# MCP3424_Temperature_board_V2.net
KiCad netlist of a schematic drawn in EAGLE
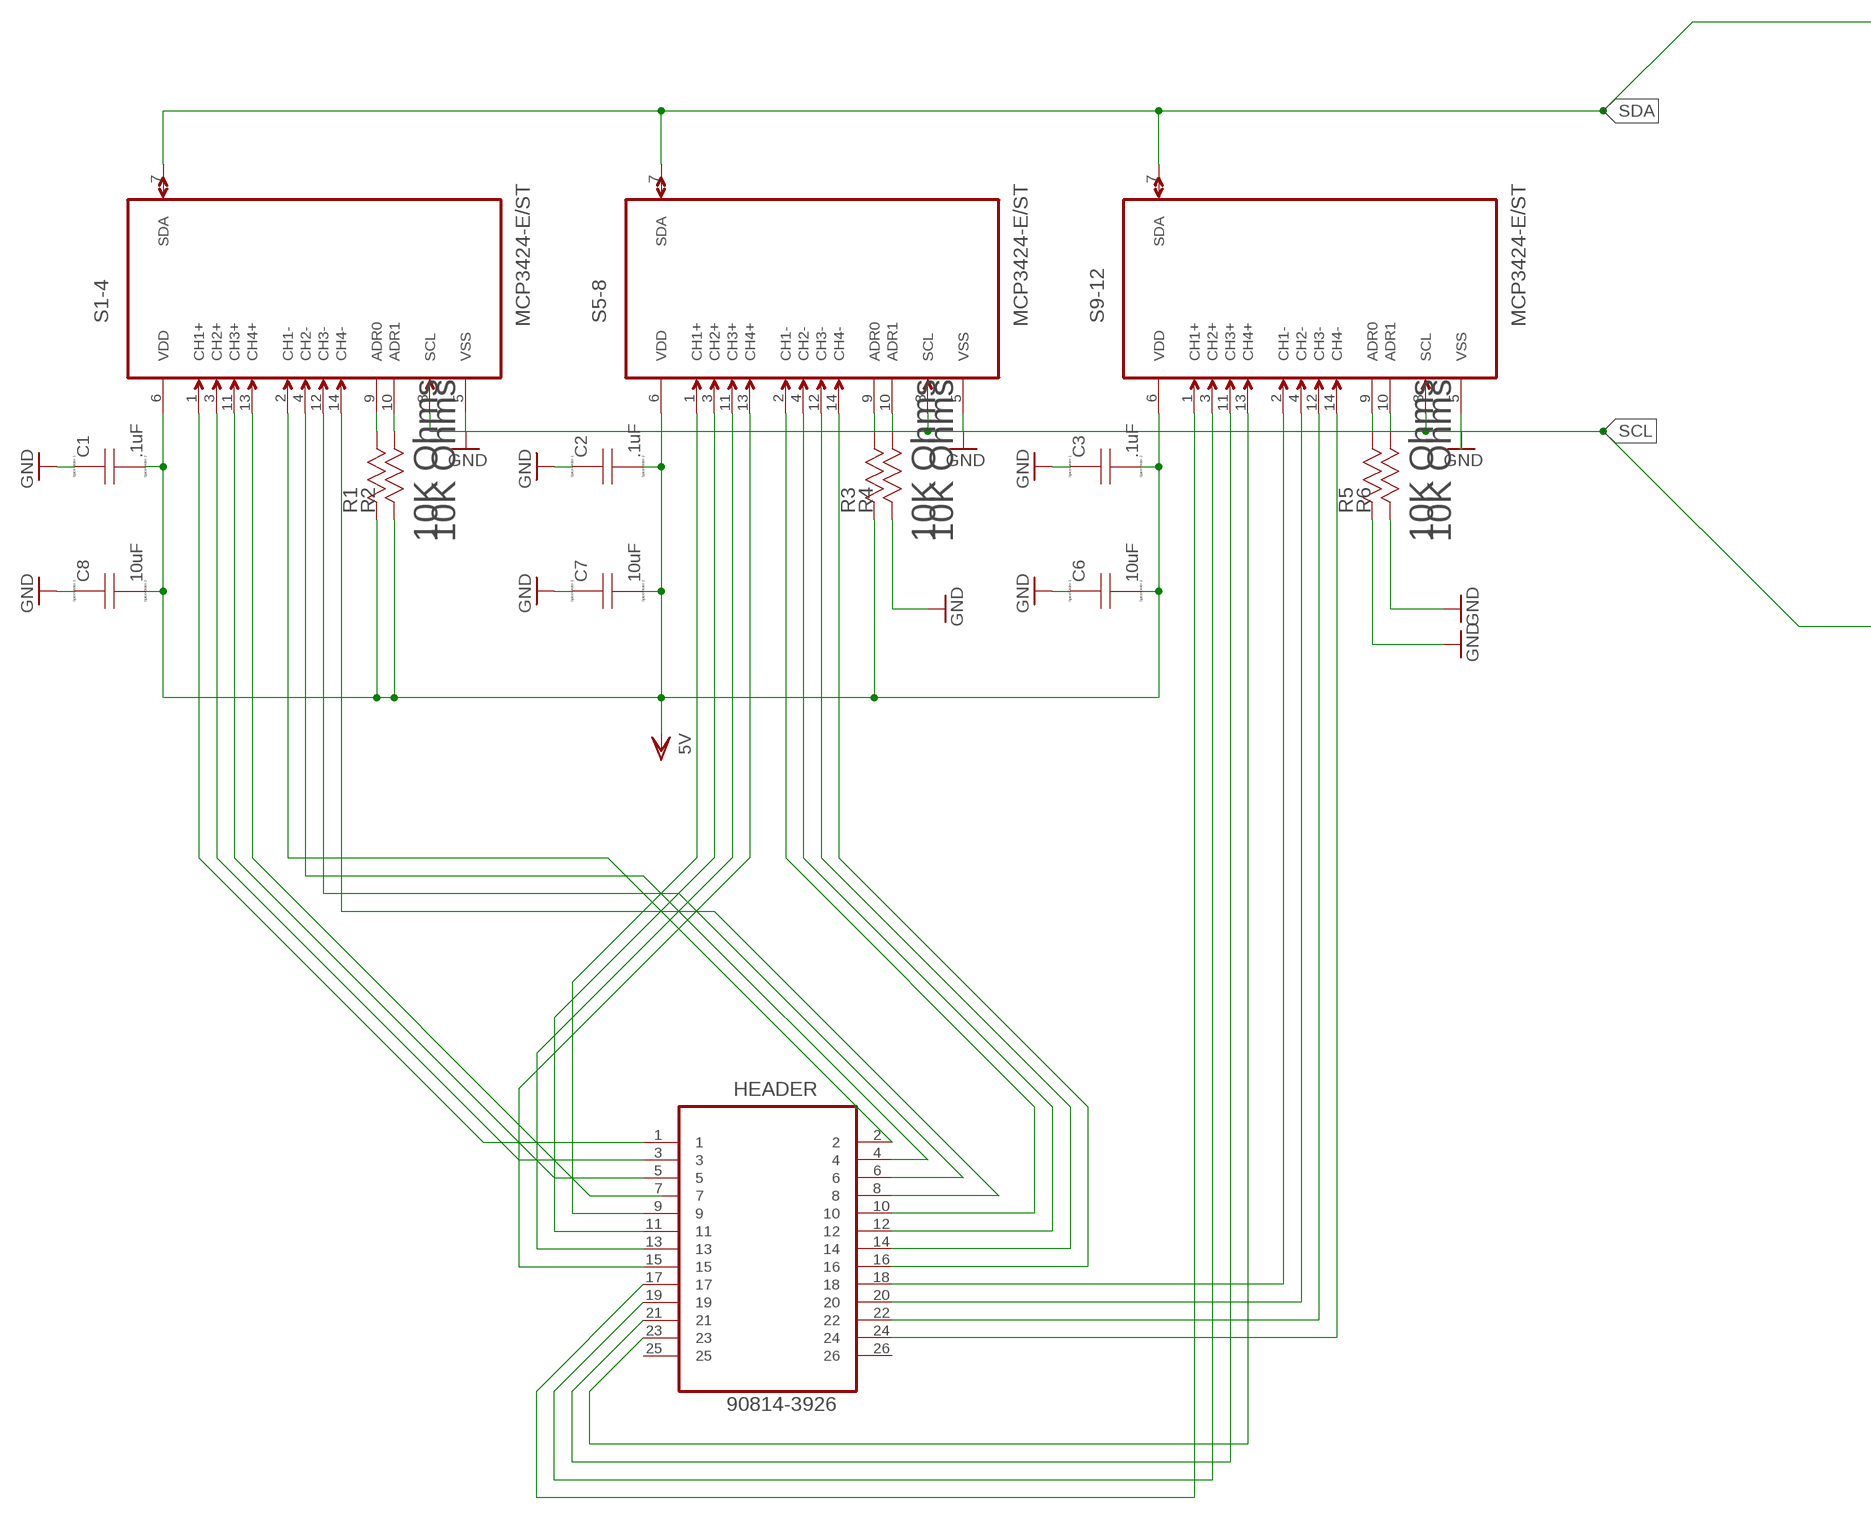
[diagram p0: schematic, sheet 1, part 1 of 2]
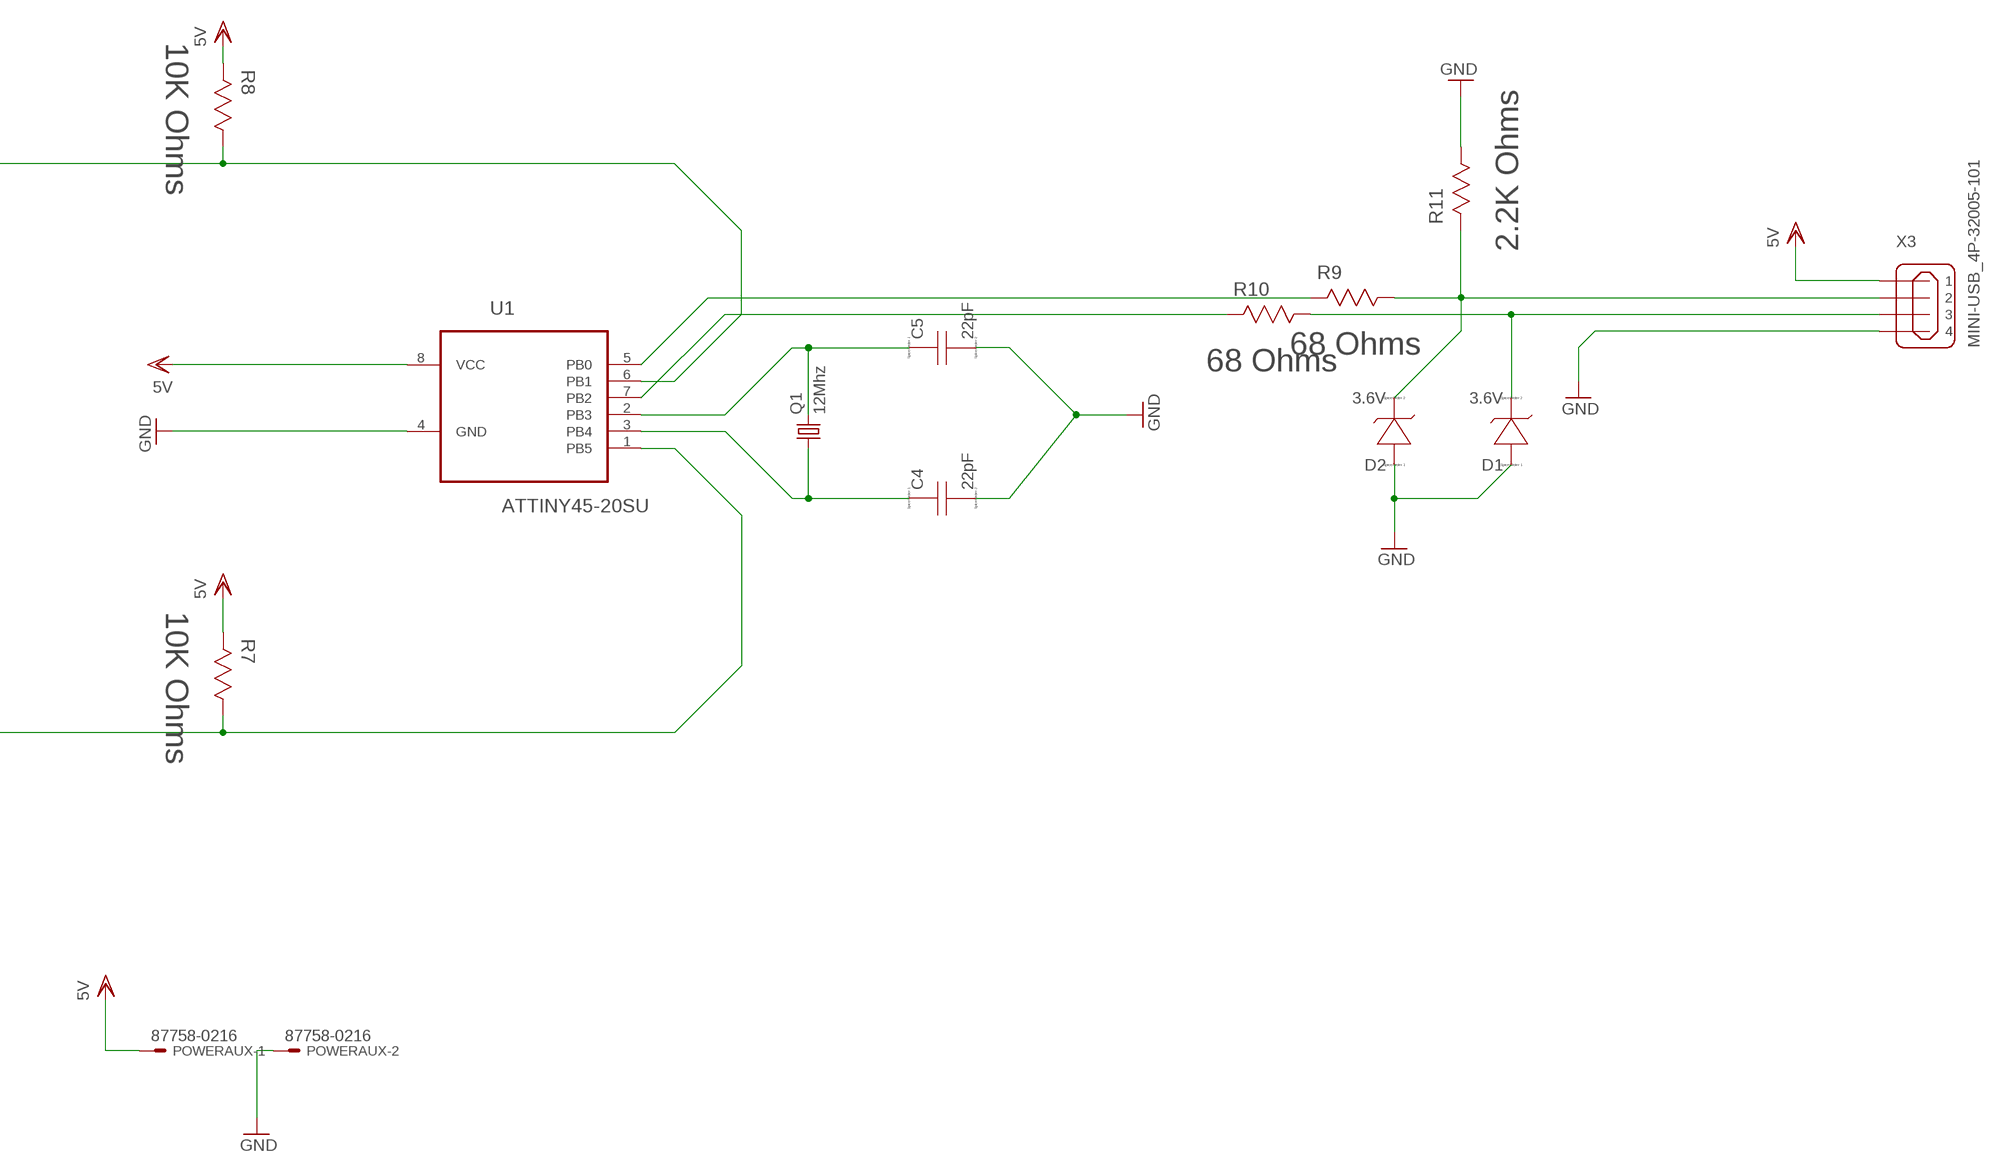
[diagram p1: schematic, sheet 1, part 2 of 2]

(export (version "E")
  (design (tool "Eeschema 10.0.6"))
  (components
    (comp (ref "C1")
      (value ".1uF")
      (footprint "eagle-import:C0805")
      (fields (field (name "MPN") "C0805C104Z3VACTU"))
      (libsource (lib "eagle-import") (part "CAP"))
    )
    (comp (ref "C2")
      (value ".1uF")
      (footprint "eagle-import:C0805")
      (fields (field (name "MPN") "C0805C104Z3VACTU"))
      (libsource (lib "eagle-import") (part "CAP"))
    )
    (comp (ref "C3")
      (value ".1uF")
      (footprint "eagle-import:C0805")
      (fields (field (name "MPN") "C0805C104Z3VACTU"))
      (libsource (lib "eagle-import") (part "CAP"))
    )
    (comp (ref "C4")
      (value "22pF")
      (footprint "eagle-import:C0805")
      (fields (field (name "MPN") "CC0805JRNPO9BN220"))
      (libsource (lib "eagle-import") (part "CAP"))
    )
    (comp (ref "C5")
      (value "22pF")
      (footprint "eagle-import:C0805")
      (fields (field (name "MPN") "CC0805JRNPO9BN220"))
      (libsource (lib "eagle-import") (part "CAP"))
    )
    (comp (ref "C6")
      (value "10uF")
      (footprint "eagle-import:C0805")
      (fields (field (name "MPN") "NOJP106M006RWJ"))
      (libsource (lib "eagle-import") (part "CAP"))
    )
    (comp (ref "C7")
      (value "10uF")
      (footprint "eagle-import:C0805")
      (fields (field (name "MPN") "NOJP106M006RWJ"))
      (libsource (lib "eagle-import") (part "CAP"))
    )
    (comp (ref "C8")
      (value "10uF")
      (footprint "eagle-import:C0805")
      (fields (field (name "MPN") "NOJP106M006RWJ"))
      (libsource (lib "eagle-import") (part "CAP"))
    )
    (comp (ref "D1")
      (value "3.6V")
      (footprint "eagle-import:SOD123")
      (fields (field (name "MPN") "MM3Z3V6T1G"))
      (libsource (lib "eagle-import") (part "ZENER"))
    )
    (comp (ref "D2")
      (value "3.6V")
      (footprint "eagle-import:SOD123")
      (fields (field (name "MPN") "MM3Z3V6T1G"))
      (libsource (lib "eagle-import") (part "ZENER"))
    )
    (comp (ref "HEADER")
      (value "90814-3926")
      (footprint "eagle-import:MOLEX_90814-3926")
      (fields
        (field (name "MF") "MOLEX")
        (field (name "MPN") "50-57-9002")
        (field (name "OC_NEWARK") "77C5436")
      )
      (libsource (lib "eagle-import") (part "90814-3926"))
    )
    (comp (ref "POWERAUX")
      (value "87758-0216")
      (footprint "eagle-import:87758-0216")
      (libsource (lib "eagle-import") (part "87758-0216"))
    )
    (comp (ref "Q1")
      (value "12Mhz")
      (footprint "eagle-import:HC49UP")
      (fields
        (field (name "MF") "Abracon Corporation")
        (field (name "MPN") "ABLS-12.000MHZ-B2-T")
        (field (name "OC_NEWARK") "13J1654")
      )
      (libsource (lib "eagle-import") (part "CRYSTALHC49UP"))
    )
    (comp (ref "R1")
      (value "10K Ohms")
      (footprint "eagle-import:RESC2013X65N")
      (fields
        (field (name "MPN") "P0805Z1002WNT0079")
        (field (name "TOLERANCE") "± 0.05 %")
        (field (name "MF") "VISHAY/DALE")
        (field (name "MPN_1") "CRCW080510K0JNEA")
        (field (name "OC_NEWARK") "52K9797")
      )
      (libsource (lib "eagle-import") (part "P0805Z1002WNT0079"))
    )
    (comp (ref "R2")
      (value "10K Ohms")
      (footprint "eagle-import:RESC2013X65N")
      (fields
        (field (name "MPN") "P0805Z1002WNT0079")
        (field (name "TOLERANCE") "± 0.05 %")
        (field (name "MF") "VISHAY/DALE")
        (field (name "MPN_1") "CRCW080510K0JNEA")
        (field (name "OC_NEWARK") "52K9797")
      )
      (libsource (lib "eagle-import") (part "P0805Z1002WNT0079"))
    )
    (comp (ref "R3")
      (value "10K Ohms")
      (footprint "eagle-import:RESC2013X65N")
      (fields
        (field (name "MPN") "P0805Z1002WNT0079")
        (field (name "TOLERANCE") "± 0.05 %")
        (field (name "MF") "VISHAY/DALE")
        (field (name "MPN_1") "CRCW080510K0JNEA")
        (field (name "OC_NEWARK") "52K9797")
      )
      (libsource (lib "eagle-import") (part "P0805Z1002WNT0079"))
    )
    (comp (ref "R4")
      (value "10K Ohms")
      (footprint "eagle-import:RESC2013X65N")
      (fields
        (field (name "MPN") "P0805Z1002WNT0079")
        (field (name "TOLERANCE") "± 0.05 %")
        (field (name "MF") "VISHAY/DALE")
        (field (name "MPN_1") "CRCW080510K0JNEA")
        (field (name "OC_NEWARK") "52K9797")
      )
      (libsource (lib "eagle-import") (part "P0805Z1002WNT0079"))
    )
    (comp (ref "R5")
      (value "10K Ohms")
      (footprint "eagle-import:RESC2013X65N")
      (fields
        (field (name "MPN") "P0805Z1002WNT0079")
        (field (name "TOLERANCE") "± 0.05 %")
        (field (name "MF") "VISHAY/DALE")
        (field (name "MPN_1") "CRCW080510K0JNEA")
        (field (name "OC_NEWARK") "52K9797")
      )
      (libsource (lib "eagle-import") (part "P0805Z1002WNT0079"))
    )
    (comp (ref "R6")
      (value "10K Ohms")
      (footprint "eagle-import:RESC2013X65N")
      (fields
        (field (name "MPN") "P0805Z1002WNT0079")
        (field (name "TOLERANCE") "± 0.05 %")
        (field (name "MF") "VISHAY/DALE")
        (field (name "MPN_1") "CRCW080510K0JNEA")
        (field (name "OC_NEWARK") "52K9797")
      )
      (libsource (lib "eagle-import") (part "P0805Z1002WNT0079"))
    )
    (comp (ref "R7")
      (value "10K Ohms")
      (footprint "eagle-import:RESC2013X65N")
      (fields
        (field (name "MPN") "P0805Z1002WNT0079")
        (field (name "TOLERANCE") "± 0.05 %")
        (field (name "MF") "VISHAY/DALE")
        (field (name "MPN_1") "CRCW080510K0JNEA")
        (field (name "OC_NEWARK") "52K9797")
      )
      (libsource (lib "eagle-import") (part "P0805Z1002WNT0079"))
    )
    (comp (ref "R8")
      (value "10K Ohms")
      (footprint "eagle-import:RESC2013X65N")
      (fields
        (field (name "MPN") "P0805Z1002WNT0079")
        (field (name "TOLERANCE") "± 0.05 %")
        (field (name "MF") "VISHAY/DALE")
        (field (name "MPN_1") "CRCW080510K0JNEA")
        (field (name "OC_NEWARK") "52K9797")
      )
      (libsource (lib "eagle-import") (part "P0805Z1002WNT0079"))
    )
    (comp (ref "R9")
      (value "68 Ohms")
      (footprint "eagle-import:RESC2013X65N")
      (fields
        (field (name "MPN") "P0805Z1002WNT0079")
        (field (name "TOLERANCE") "± 0.05 %")
        (field (name "MPN_1") "ERJ-B3BFR68V")
        (field (name "OC_NEWARK") "32R9312")
      )
      (libsource (lib "eagle-import") (part "P0805Z1002WNT0079"))
    )
    (comp (ref "R10")
      (value "68 Ohms")
      (footprint "eagle-import:RESC2013X65N")
      (fields
        (field (name "MPN") "P0805Z1002WNT0079")
        (field (name "TOLERANCE") "± 0.05 %")
        (field (name "MPN_1") "ERJ-B3BFR68V")
        (field (name "OC_NEWARK") "32R9312")
      )
      (libsource (lib "eagle-import") (part "P0805Z1002WNT0079"))
    )
    (comp (ref "R11")
      (value "2.2K Ohms")
      (footprint "eagle-import:RESC2013X65N")
      (fields
        (field (name "MPN") "P0805Z1002WNT0079")
        (field (name "TOLERANCE") "± 0.05 %")
        (field (name "MF") "VISHAY/DALE")
        (field (name "MPN_1") "CRCW08052K20FKEA")
        (field (name "OC_NEWARK") "52K9951")
      )
      (libsource (lib "eagle-import") (part "P0805Z1002WNT0079"))
    )
    (comp (ref "S1-4")
      (value "MCP3424-E/ST")
      (footprint "eagle-import:SOP65P640X120-14N")
      (libsource (lib "eagle-import") (part "MCP3424-E/ST"))
    )
    (comp (ref "S5-8")
      (value "MCP3424-E/ST")
      (footprint "eagle-import:SOP65P640X120-14N")
      (libsource (lib "eagle-import") (part "MCP3424-E/ST"))
    )
    (comp (ref "S9-12")
      (value "MCP3424-E/ST")
      (footprint "eagle-import:SOP65P640X120-14N")
      (libsource (lib "eagle-import") (part "MCP3424-E/ST"))
    )
    (comp (ref "U1")
      (value "ATTINY45-20SU")
      (footprint "eagle-import:SOIC127P798X216-8N")
      (fields (field (name "OC_NEWARK") "68T3731"))
      (libsource (lib "eagle-import") (part "ATTINY45-20SU"))
    )
    (comp (ref "X3")
      (value "MINI-USB_4P-32005-101")
      (footprint "eagle-import:32005-101")
      (fields (field (name "MPN") "651005136421") (field (name "OC_NEWARK") "12T8884"))
      (libsource (lib "eagle-import") (part "MINI-USB_4P-32005-101"))
    )
  )
  (nets
    (net (code "1") (name "5V") (class "Default")
      (node (ref "C1") (pin "2") (pinfunction "B_2") (pintype "passive"))
      (node (ref "C2") (pin "2") (pinfunction "B_2") (pintype "passive"))
      (node (ref "C3") (pin "2") (pinfunction "B_2") (pintype "passive"))
      (node (ref "C6") (pin "2") (pinfunction "B_2") (pintype "passive"))
      (node (ref "C7") (pin "2") (pinfunction "B_2") (pintype "passive"))
      (node (ref "C8") (pin "2") (pinfunction "B_2") (pintype "passive"))
      (node (ref "POWERAUX") (pin "1") (pinfunction "S_1") (pintype "passive"))
      (node (ref "R1") (pin "2") (pinfunction "2_2") (pintype "passive"))
      (node (ref "R2") (pin "2") (pinfunction "2_2") (pintype "passive"))
      (node (ref "R3") (pin "2") (pinfunction "2_2") (pintype "passive"))
      (node (ref "R7") (pin "2") (pinfunction "2_2") (pintype "passive"))
      (node (ref "R8") (pin "2") (pinfunction "2_2") (pintype "passive"))
      (node (ref "S1-4") (pin "6") (pinfunction "VDD_6") (pintype "power_in"))
      (node (ref "S5-8") (pin "6") (pinfunction "VDD_6") (pintype "power_in"))
      (node (ref "S9-12") (pin "6") (pinfunction "VDD_6") (pintype "power_in"))
      (node (ref "U1") (pin "8") (pinfunction "VCC_8") (pintype "power_in"))
      (node (ref "X3") (pin "1") (pinfunction "1_1") (pintype "passive"))
    )
    (net (code "2") (name "GND") (class "Default")
      (node (ref "C1") (pin "1") (pinfunction "A_1") (pintype "passive"))
      (node (ref "C2") (pin "1") (pinfunction "A_1") (pintype "passive"))
      (node (ref "C3") (pin "1") (pinfunction "A_1") (pintype "passive"))
      (node (ref "C4") (pin "2") (pinfunction "B_2") (pintype "passive"))
      (node (ref "C5") (pin "2") (pinfunction "B_2") (pintype "passive"))
      (node (ref "C6") (pin "1") (pinfunction "A_1") (pintype "passive"))
      (node (ref "C7") (pin "1") (pinfunction "A_1") (pintype "passive"))
      (node (ref "C8") (pin "1") (pinfunction "A_1") (pintype "passive"))
      (node (ref "D1") (pin "A") (pinfunction "+_A") (pintype "passive"))
      (node (ref "D2") (pin "A") (pinfunction "+_A") (pintype "passive"))
      (node (ref "POWERAUX") (pin "2") (pinfunction "S_2") (pintype "passive"))
      (node (ref "R11") (pin "1") (pinfunction "1_1") (pintype "passive"))
      (node (ref "R4") (pin "2") (pinfunction "2_2") (pintype "passive"))
      (node (ref "R5") (pin "2") (pinfunction "2_2") (pintype "passive"))
      (node (ref "R6") (pin "2") (pinfunction "2_2") (pintype "passive"))
      (node (ref "S1-4") (pin "5") (pinfunction "VSS_5") (pintype "power_in"))
      (node (ref "S5-8") (pin "5") (pinfunction "VSS_5") (pintype "power_in"))
      (node (ref "U1") (pin "4") (pinfunction "GND_4") (pintype "passive"))
      (node (ref "X3") (pin "4") (pinfunction "4_4") (pintype "passive"))
    )
    (net (code "3") (name "Net-(C4-A)") (class "Default")
      (node (ref "C4") (pin "1") (pinfunction "A_1") (pintype "passive"))
      (node (ref "Q1") (pin "1") (pinfunction "1_1") (pintype "passive"))
      (node (ref "U1") (pin "3") (pinfunction "PB4_3") (pintype "bidirectional"))
    )
    (net (code "4") (name "Net-(C5-A)") (class "Default")
      (node (ref "C5") (pin "1") (pinfunction "A_1") (pintype "passive"))
      (node (ref "Q1") (pin "2") (pinfunction "2_2") (pintype "passive"))
      (node (ref "U1") (pin "2") (pinfunction "PB3_2") (pintype "bidirectional"))
    )
    (net (code "5") (name "Net-(D1--)") (class "Default")
      (node (ref "D1") (pin "C") (pinfunction "-_C") (pintype "passive"))
      (node (ref "R10") (pin "1") (pinfunction "1_1") (pintype "passive"))
      (node (ref "X3") (pin "3") (pinfunction "3_3") (pintype "passive"))
    )
    (net (code "6") (name "Net-(D2--)") (class "Default")
      (node (ref "D2") (pin "C") (pinfunction "-_C") (pintype "passive"))
      (node (ref "R11") (pin "2") (pinfunction "2_2") (pintype "passive"))
      (node (ref "R9") (pin "1") (pinfunction "1_1") (pintype "passive"))
      (node (ref "X3") (pin "2") (pinfunction "2_2") (pintype "passive"))
    )
    (net (code "7") (name "Net-(S1-4-ADR0)") (class "Default")
      (node (ref "R1") (pin "1") (pinfunction "1_1") (pintype "passive"))
      (node (ref "S1-4") (pin "9") (pinfunction "ADR0_9") (pintype "input"))
    )
    (net (code "8") (name "Net-(S1-4-ADR1)") (class "Default")
      (node (ref "R2") (pin "1") (pinfunction "1_1") (pintype "passive"))
      (node (ref "S1-4") (pin "10") (pinfunction "ADR1_10") (pintype "input"))
    )
    (net (code "9") (name "Net-(S1-4-CH1+)") (class "Default")
      (node (ref "HEADER") (pin "1") (pinfunction "1_1") (pintype "passive"))
      (node (ref "S1-4") (pin "1") (pinfunction "CH1+_1") (pintype "input"))
    )
    (net (code "10") (name "Net-(S1-4-CH1-)") (class "Default")
      (node (ref "HEADER") (pin "2") (pinfunction "2_2") (pintype "passive"))
      (node (ref "S1-4") (pin "2") (pinfunction "CH1-_2") (pintype "input"))
    )
    (net (code "11") (name "Net-(S1-4-CH2+)") (class "Default")
      (node (ref "HEADER") (pin "3") (pinfunction "3_3") (pintype "passive"))
      (node (ref "S1-4") (pin "3") (pinfunction "CH2+_3") (pintype "input"))
    )
    (net (code "12") (name "Net-(S1-4-CH2-)") (class "Default")
      (node (ref "HEADER") (pin "4") (pinfunction "4_4") (pintype "passive"))
      (node (ref "S1-4") (pin "4") (pinfunction "CH2-_4") (pintype "input"))
    )
    (net (code "13") (name "Net-(S1-4-CH3+)") (class "Default")
      (node (ref "HEADER") (pin "5") (pinfunction "5_5") (pintype "passive"))
      (node (ref "S1-4") (pin "11") (pinfunction "CH3+_11") (pintype "input"))
    )
    (net (code "14") (name "Net-(S1-4-CH3-)") (class "Default")
      (node (ref "HEADER") (pin "6") (pinfunction "6_6") (pintype "passive"))
      (node (ref "S1-4") (pin "12") (pinfunction "CH3-_12") (pintype "input"))
    )
    (net (code "15") (name "Net-(S1-4-CH4-)") (class "Default")
      (node (ref "HEADER") (pin "8") (pinfunction "8_8") (pintype "passive"))
      (node (ref "S1-4") (pin "14") (pinfunction "CH4-_14") (pintype "input"))
    )
    (net (code "16") (name "Net-(S5-8-ADR0)") (class "Default")
      (node (ref "R3") (pin "1") (pinfunction "1_1") (pintype "passive"))
      (node (ref "S5-8") (pin "9") (pinfunction "ADR0_9") (pintype "input"))
    )
    (net (code "17") (name "Net-(S5-8-ADR1)") (class "Default")
      (node (ref "R4") (pin "1") (pinfunction "1_1") (pintype "passive"))
      (node (ref "S5-8") (pin "10") (pinfunction "ADR1_10") (pintype "input"))
    )
    (net (code "18") (name "Net-(S5-8-CH1+)") (class "Default")
      (node (ref "HEADER") (pin "9") (pinfunction "9_9") (pintype "passive"))
      (node (ref "S5-8") (pin "1") (pinfunction "CH1+_1") (pintype "input"))
    )
    (net (code "19") (name "Net-(S5-8-CH1-)") (class "Default")
      (node (ref "HEADER") (pin "10") (pinfunction "10_10") (pintype "passive"))
      (node (ref "S5-8") (pin "2") (pinfunction "CH1-_2") (pintype "input"))
    )
    (net (code "20") (name "Net-(S5-8-CH2+)") (class "Default")
      (node (ref "HEADER") (pin "11") (pinfunction "11_11") (pintype "passive"))
      (node (ref "S5-8") (pin "3") (pinfunction "CH2+_3") (pintype "input"))
    )
    (net (code "21") (name "Net-(S5-8-CH2-)") (class "Default")
      (node (ref "HEADER") (pin "12") (pinfunction "12_12") (pintype "passive"))
      (node (ref "S5-8") (pin "4") (pinfunction "CH2-_4") (pintype "input"))
    )
    (net (code "22") (name "Net-(S5-8-CH3+)") (class "Default")
      (node (ref "HEADER") (pin "13") (pinfunction "13_13") (pintype "passive"))
      (node (ref "S5-8") (pin "11") (pinfunction "CH3+_11") (pintype "input"))
    )
    (net (code "23") (name "Net-(S5-8-CH3-)") (class "Default")
      (node (ref "HEADER") (pin "14") (pinfunction "14_14") (pintype "passive"))
      (node (ref "S5-8") (pin "12") (pinfunction "CH3-_12") (pintype "input"))
    )
    (net (code "24") (name "Net-(S5-8-CH4+)") (class "Default")
      (node (ref "HEADER") (pin "15") (pinfunction "15_15") (pintype "passive"))
      (node (ref "S5-8") (pin "13") (pinfunction "CH4+_13") (pintype "input"))
    )
    (net (code "25") (name "Net-(S5-8-CH4-)") (class "Default")
      (node (ref "HEADER") (pin "16") (pinfunction "16_16") (pintype "passive"))
      (node (ref "S5-8") (pin "14") (pinfunction "CH4-_14") (pintype "input"))
    )
    (net (code "26") (name "Net-(S9-12-ADR0)") (class "Default")
      (node (ref "R5") (pin "1") (pinfunction "1_1") (pintype "passive"))
      (node (ref "S9-12") (pin "9") (pinfunction "ADR0_9") (pintype "input"))
    )
    (net (code "27") (name "Net-(S9-12-ADR1)") (class "Default")
      (node (ref "R6") (pin "1") (pinfunction "1_1") (pintype "passive"))
      (node (ref "S9-12") (pin "10") (pinfunction "ADR1_10") (pintype "input"))
    )
    (net (code "28") (name "Net-(S9-12-CH1+)") (class "Default")
      (node (ref "HEADER") (pin "17") (pinfunction "17_17") (pintype "passive"))
      (node (ref "S9-12") (pin "1") (pinfunction "CH1+_1") (pintype "input"))
    )
    (net (code "29") (name "Net-(S9-12-CH1-)") (class "Default")
      (node (ref "HEADER") (pin "18") (pinfunction "18_18") (pintype "passive"))
      (node (ref "S9-12") (pin "2") (pinfunction "CH1-_2") (pintype "input"))
    )
    (net (code "30") (name "Net-(S9-12-CH2+)") (class "Default")
      (node (ref "HEADER") (pin "19") (pinfunction "19_19") (pintype "passive"))
      (node (ref "S9-12") (pin "3") (pinfunction "CH2+_3") (pintype "input"))
    )
    (net (code "31") (name "Net-(S9-12-CH2-)") (class "Default")
      (node (ref "HEADER") (pin "20") (pinfunction "20_20") (pintype "passive"))
      (node (ref "S9-12") (pin "4") (pinfunction "CH2-_4") (pintype "input"))
    )
    (net (code "32") (name "Net-(S9-12-CH3+)") (class "Default")
      (node (ref "HEADER") (pin "21") (pinfunction "21_21") (pintype "passive"))
      (node (ref "S9-12") (pin "11") (pinfunction "CH3+_11") (pintype "input"))
    )
    (net (code "33") (name "Net-(S9-12-CH3-)") (class "Default")
      (node (ref "HEADER") (pin "22") (pinfunction "22_22") (pintype "passive"))
      (node (ref "S9-12") (pin "12") (pinfunction "CH3-_12") (pintype "input"))
    )
    (net (code "34") (name "Net-(S9-12-CH4+)") (class "Default")
      (node (ref "HEADER") (pin "23") (pinfunction "23_23") (pintype "passive"))
      (node (ref "S9-12") (pin "13") (pinfunction "CH4+_13") (pintype "input"))
    )
    (net (code "35") (name "Net-(S9-12-CH4-)") (class "Default")
      (node (ref "HEADER") (pin "24") (pinfunction "24_24") (pintype "passive"))
      (node (ref "S9-12") (pin "14") (pinfunction "CH4-_14") (pintype "input"))
    )
    (net (code "36") (name "Net-(U1-PB0)") (class "Default")
      (node (ref "R9") (pin "2") (pinfunction "2_2") (pintype "passive"))
      (node (ref "U1") (pin "5") (pinfunction "PB0_5") (pintype "bidirectional"))
    )
    (net (code "37") (name "Net-(U1-PB2)") (class "Default")
      (node (ref "R10") (pin "2") (pinfunction "2_2") (pintype "passive"))
      (node (ref "U1") (pin "7") (pinfunction "PB2_7") (pintype "bidirectional"))
    )
    (net (code "38") (name "SCL") (class "Default")
      (node (ref "R7") (pin "1") (pinfunction "1_1") (pintype "passive"))
      (node (ref "S1-4") (pin "8") (pinfunction "SCL_8") (pintype "input"))
      (node (ref "S5-8") (pin "8") (pinfunction "SCL_8") (pintype "input"))
      (node (ref "S9-12") (pin "8") (pinfunction "SCL_8") (pintype "input"))
      (node (ref "U1") (pin "1") (pinfunction "PB5_1") (pintype "bidirectional"))
    )
    (net (code "39") (name "SDA") (class "Default")
      (node (ref "R8") (pin "1") (pinfunction "1_1") (pintype "passive"))
      (node (ref "S1-4") (pin "7") (pinfunction "SDA_7") (pintype "bidirectional"))
      (node (ref "S5-8") (pin "7") (pinfunction "SDA_7") (pintype "bidirectional"))
      (node (ref "S9-12") (pin "7") (pinfunction "SDA_7") (pintype "bidirectional"))
      (node (ref "U1") (pin "6") (pinfunction "PB1_6") (pintype "bidirectional"))
    )
    (net (code "40") (name "unconnected-(HEADER-Pad7)") (class "Default")
      (node (ref "HEADER") (pin "7") (pinfunction "7_7") (pintype "passive"))
    )
    (net (code "41") (name "unconnected-(HEADER-Pad25)") (class "Default")
      (node (ref "HEADER") (pin "25") (pinfunction "25_25") (pintype "passive"))
    )
    (net (code "42") (name "unconnected-(HEADER-Pad26)") (class "Default")
      (node (ref "HEADER") (pin "26") (pinfunction "26_26") (pintype "passive"))
    )
    (net (code "43") (name "unconnected-(S1-4-CH4+-Pad13)") (class "Default")
      (node (ref "S1-4") (pin "13") (pinfunction "CH4+_13") (pintype "input"))
    )
    (net (code "44") (name "unconnected-(S9-12-VSS-Pad5)") (class "Default")
      (node (ref "S9-12") (pin "5") (pinfunction "VSS_5") (pintype "power_in"))
    )
  )
)
